# ProPrj_EMU_Multi_LED_Button_PCB_rev1_0.net
KiCad netlist of a schematic drawn in EasyEDA Pro
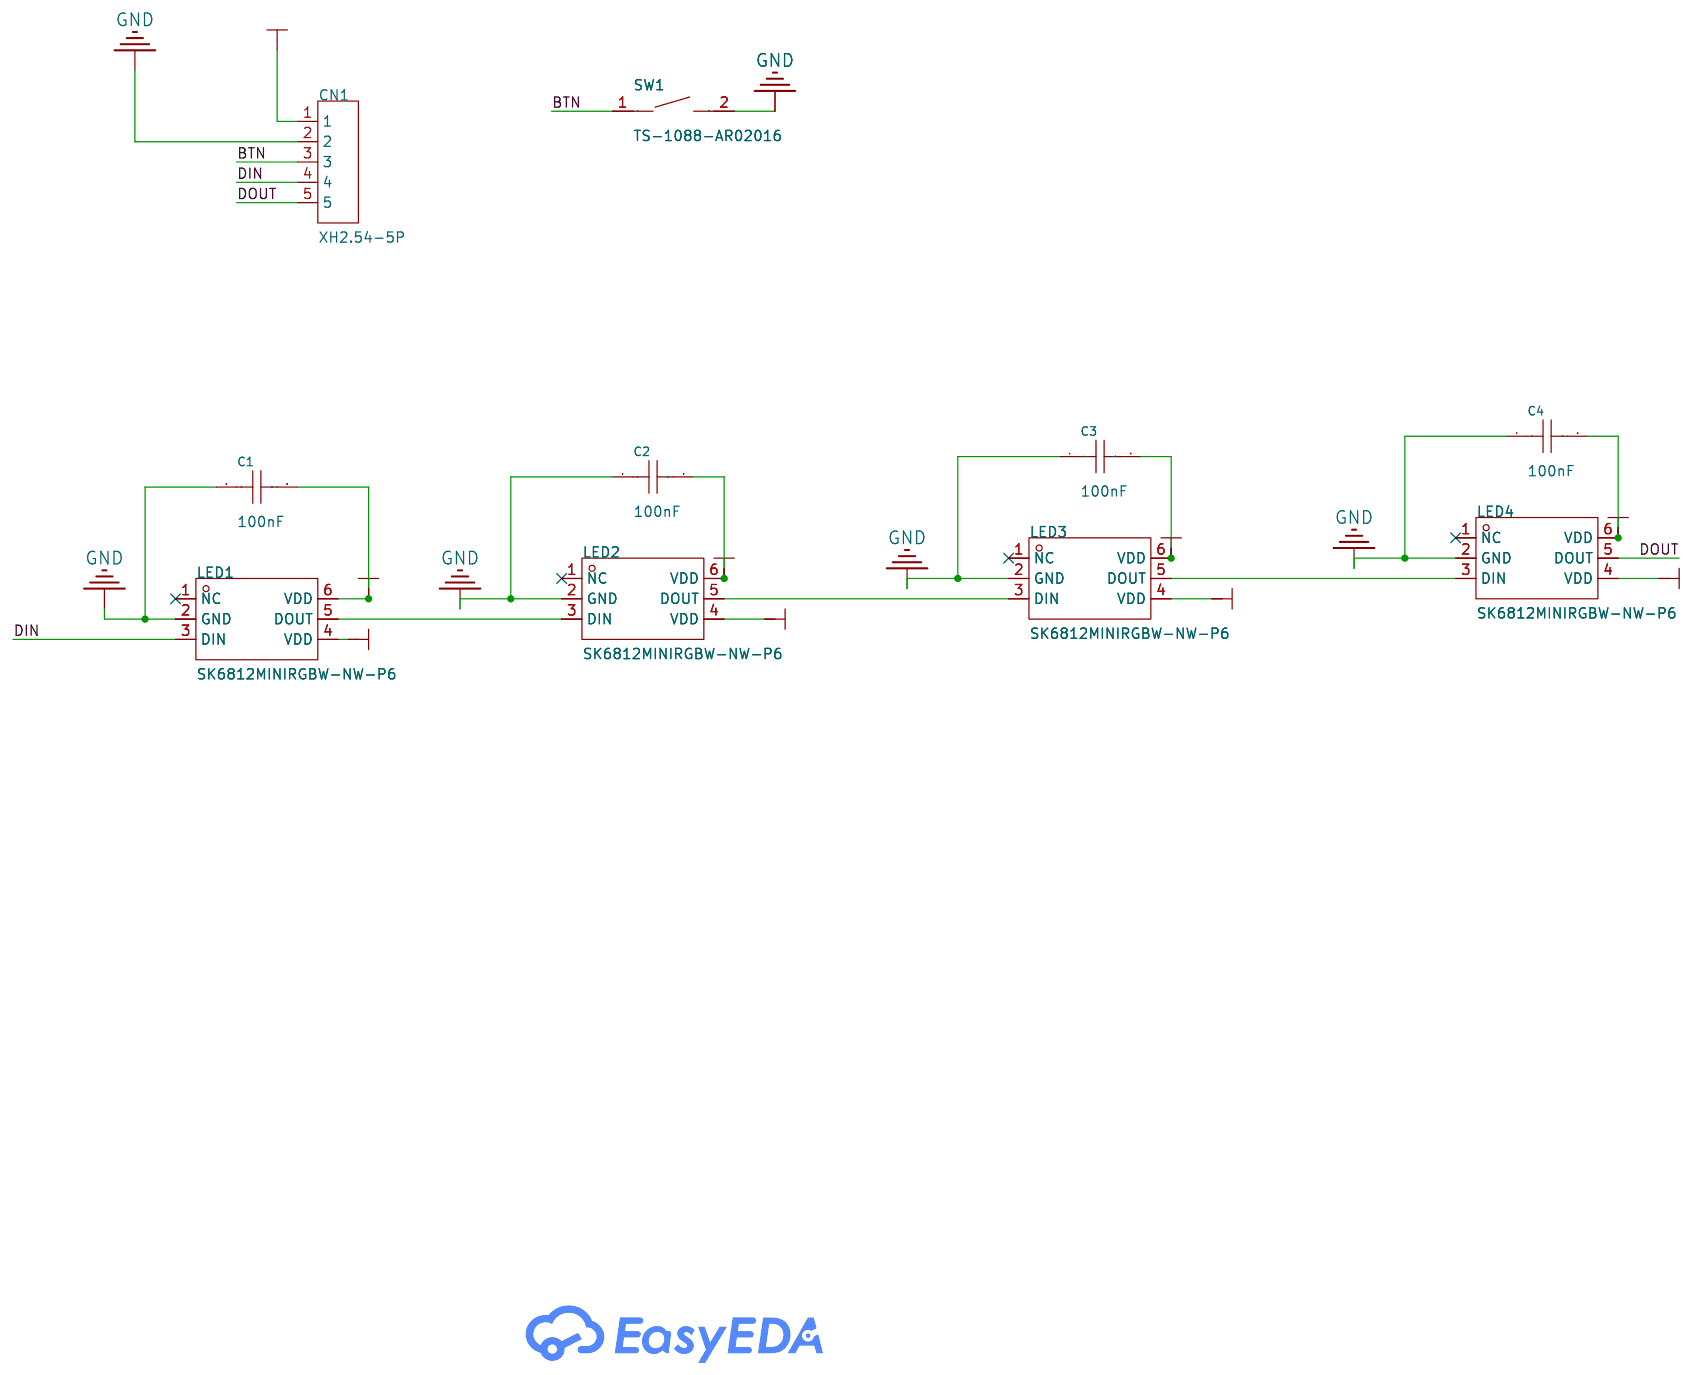
[diagram p0: schematic sheet]

(export (version "E")
  (design (tool "Eeschema 10.0.6"))
  (components
    (comp (ref "C1")
      (value "100nF")
      (footprint "easyedapro:C0603")
      (description "Capacitance:100nF Tolerance:±10% Tolerance:±10% Voltage Rating:50V Temperature Coefficient:X7R")
      (fields
        (field (name "Manufacturer Part") "CL10B104KB8NNNC")
        (field (name "Manufacturer") "SAMSUNG(三星)")
      )
      (libsource (lib "easyedapro") (part "CL10B104KB8NNNC"))
    )
    (comp (ref "C2")
      (value "100nF")
      (footprint "easyedapro:C0603")
      (description "Capacitance:100nF Tolerance:±10% Tolerance:±10% Voltage Rating:50V Temperature Coefficient:X7R")
      (fields
        (field (name "Manufacturer Part") "CL10B104KB8NNNC")
        (field (name "Manufacturer") "SAMSUNG(三星)")
      )
      (libsource (lib "easyedapro") (part "CL10B104KB8NNNC"))
    )
    (comp (ref "C3")
      (value "100nF")
      (footprint "easyedapro:C0603")
      (description "Capacitance:100nF Tolerance:±10% Tolerance:±10% Voltage Rating:50V Temperature Coefficient:X7R")
      (fields
        (field (name "Manufacturer Part") "CL10B104KB8NNNC")
        (field (name "Manufacturer") "SAMSUNG(三星)")
      )
      (libsource (lib "easyedapro") (part "CL10B104KB8NNNC"))
    )
    (comp (ref "C4")
      (value "100nF")
      (footprint "easyedapro:C0603")
      (description "Capacitance:100nF Tolerance:±10% Tolerance:±10% Voltage Rating:50V Temperature Coefficient:X7R")
      (fields
        (field (name "Manufacturer Part") "CL10B104KB8NNNC")
        (field (name "Manufacturer") "SAMSUNG(三星)")
      )
      (libsource (lib "easyedapro") (part "CL10B104KB8NNNC"))
    )
    (comp (ref "CN1")
      (value "XH2.54-5P")
      (footprint "easyedapro:CONN-TH_5P-P2.54_C9900008095")
      (libsource (lib "easyedapro") (part "XH2.54-5P_C9900017328"))
    )
    (comp (ref "LED1")
      (value "SK6812MINIRGBW-NW-P6")
      (footprint "easyedapro:LED-ARRAY-SMD_6P-L3.7-W3.5-TL-RD-1")
      (fields (field (name "Manufacturer") "欧思科光电"))
      (libsource (lib "easyedapro") (part "SK6812MINIRGBW-NW-P6"))
    )
    (comp (ref "LED2")
      (value "SK6812MINIRGBW-NW-P6")
      (footprint "easyedapro:LED-ARRAY-SMD_6P-L3.7-W3.5-TL-RD-1")
      (fields (field (name "Manufacturer") "欧思科光电"))
      (libsource (lib "easyedapro") (part "SK6812MINIRGBW-NW-P6"))
    )
    (comp (ref "LED3")
      (value "SK6812MINIRGBW-NW-P6")
      (footprint "easyedapro:LED-ARRAY-SMD_6P-L3.7-W3.5-TL-RD-1")
      (fields (field (name "Manufacturer") "欧思科光电"))
      (libsource (lib "easyedapro") (part "SK6812MINIRGBW-NW-P6"))
    )
    (comp (ref "LED4")
      (value "SK6812MINIRGBW-NW-P6")
      (footprint "easyedapro:LED-ARRAY-SMD_6P-L3.7-W3.5-TL-RD-1")
      (fields (field (name "Manufacturer") "欧思科光电"))
      (libsource (lib "easyedapro") (part "SK6812MINIRGBW-NW-P6"))
    )
    (comp (ref "SW1")
      (value "TS-1088-AR02016")
      (footprint "easyedapro:SW-SMD_L3.9-W3.0-P4.45")
      (fields (field (name "Manufacturer") "XUNPU(讯普)"))
      (libsource (lib "easyedapro") (part "TS-1088-AR02016"))
    )
  )
  (nets
    (net (code "1") (name "/BTN") (class "Default")
      (node (ref "CN1") (pin "3") (pinfunction "3_3") (pintype "unspecified"))
      (node (ref "SW1") (pin "1") (pinfunction "1_1") (pintype "unspecified"))
    )
    (net (code "2") (name "/DIN") (class "Default")
      (node (ref "CN1") (pin "4") (pinfunction "4_4") (pintype "unspecified"))
      (node (ref "LED1") (pin "3") (pinfunction "DIN_3") (pintype "unspecified"))
    )
    (net (code "3") (name "/DOUT") (class "Default")
      (node (ref "CN1") (pin "5") (pinfunction "5_5") (pintype "unspecified"))
      (node (ref "LED4") (pin "5") (pinfunction "DOUT_5") (pintype "unspecified"))
    )
    (net (code "4") (name "GND") (class "Default")
      (node (ref "C1") (pin "1") (pinfunction "1_1") (pintype "input"))
      (node (ref "C2") (pin "1") (pinfunction "1_1") (pintype "input"))
      (node (ref "C3") (pin "1") (pinfunction "1_1") (pintype "input"))
      (node (ref "C4") (pin "1") (pinfunction "1_1") (pintype "input"))
      (node (ref "CN1") (pin "2") (pinfunction "2_2") (pintype "unspecified"))
      (node (ref "LED1") (pin "2") (pinfunction "GND_2") (pintype "unspecified"))
      (node (ref "LED2") (pin "2") (pinfunction "GND_2") (pintype "unspecified"))
      (node (ref "LED3") (pin "2") (pinfunction "GND_2") (pintype "unspecified"))
      (node (ref "LED4") (pin "2") (pinfunction "GND_2") (pintype "unspecified"))
      (node (ref "SW1") (pin "2") (pinfunction "2_2") (pintype "unspecified"))
    )
    (net (code "5") (name "Net-(LED1-DOUT)") (class "Default")
      (node (ref "LED1") (pin "5") (pinfunction "DOUT_5") (pintype "unspecified"))
      (node (ref "LED2") (pin "3") (pinfunction "DIN_3") (pintype "unspecified"))
    )
    (net (code "6") (name "Net-(LED2-DOUT)") (class "Default")
      (node (ref "LED2") (pin "5") (pinfunction "DOUT_5") (pintype "unspecified"))
      (node (ref "LED3") (pin "3") (pinfunction "DIN_3") (pintype "unspecified"))
    )
    (net (code "7") (name "Net-(LED3-DOUT)") (class "Default")
      (node (ref "LED3") (pin "5") (pinfunction "DOUT_5") (pintype "unspecified"))
      (node (ref "LED4") (pin "3") (pinfunction "DIN_3") (pintype "unspecified"))
    )
    (net (code "8") (name "VCC") (class "Default")
      (node (ref "C1") (pin "2") (pinfunction "2_2") (pintype "input"))
      (node (ref "C2") (pin "2") (pinfunction "2_2") (pintype "input"))
      (node (ref "C3") (pin "2") (pinfunction "2_2") (pintype "input"))
      (node (ref "C4") (pin "2") (pinfunction "2_2") (pintype "input"))
      (node (ref "CN1") (pin "1") (pinfunction "1_1") (pintype "unspecified"))
      (node (ref "LED1") (pin "4") (pinfunction "VDD_4") (pintype "unspecified"))
      (node (ref "LED1") (pin "6") (pinfunction "VDD_6") (pintype "unspecified"))
      (node (ref "LED2") (pin "4") (pinfunction "VDD_4") (pintype "unspecified"))
      (node (ref "LED2") (pin "6") (pinfunction "VDD_6") (pintype "unspecified"))
      (node (ref "LED3") (pin "4") (pinfunction "VDD_4") (pintype "unspecified"))
      (node (ref "LED3") (pin "6") (pinfunction "VDD_6") (pintype "unspecified"))
      (node (ref "LED4") (pin "4") (pinfunction "VDD_4") (pintype "unspecified"))
      (node (ref "LED4") (pin "6") (pinfunction "VDD_6") (pintype "unspecified"))
    )
    (net (code "9") (name "unconnected-(LED1-NC-Pad1)") (class "Default")
      (node (ref "LED1") (pin "1") (pinfunction "NC_1") (pintype "unspecified+no_connect"))
    )
    (net (code "10") (name "unconnected-(LED2-NC-Pad1)") (class "Default")
      (node (ref "LED2") (pin "1") (pinfunction "NC_1") (pintype "unspecified+no_connect"))
    )
    (net (code "11") (name "unconnected-(LED3-NC-Pad1)") (class "Default")
      (node (ref "LED3") (pin "1") (pinfunction "NC_1") (pintype "unspecified+no_connect"))
    )
    (net (code "12") (name "unconnected-(LED4-NC-Pad1)") (class "Default")
      (node (ref "LED4") (pin "1") (pinfunction "NC_1") (pintype "unspecified+no_connect"))
    )
  )
)
